# design.net
KiCad netlist of a schematic drawn in Altium Designer
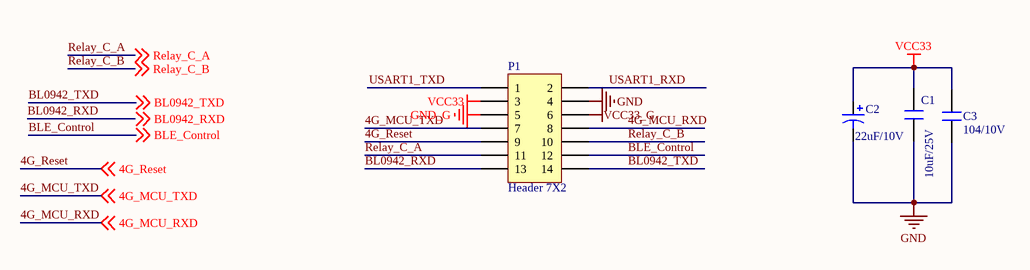
[diagram p0: 连接.SchDoc]

(export (version "E")
  (design (tool "Eeschema 10.0.6"))
  (components
    (comp (ref "C1") (value "10uF/25V") (footprint "0603R") (libsource (lib "ES_Schematic") (part "CAP")))
    (comp (ref "C2")
      (value "22uF/10V")
      (footprint "0805R")
      (description "Polarized Capacitor (Radial)")
      (fields (field (name "PUBLISHER") "Altium Limited"))
      (libsource (lib "Miscellaneous Devices") (part "Cap Pol1"))
    )
    (comp (ref "C3") (value "104/10V") (footprint "0603R") (libsource (lib "ES_Schematic") (part "CAP_1")))
    (comp (ref "P1")
      (value "Header 7X2")
      (footprint "HDR2X7")
      (description "Header, 7-Pin, Dual row")
      (fields (field (name "PUBLISHER") "Altium Limited"))
      (libsource (lib "Miscellaneous Connectors") (part "Header 7X2"))
    )
  )
  (nets
    (net (code "1") (name "/USART1_RXD") (class "Default")
      (node (ref "P1") (pin "2") (pinfunction "2_2") (pintype "passive"))
    )
    (net (code "2") (name "/USART1_TXD") (class "Default")
      (node (ref "P1") (pin "1") (pinfunction "1_1") (pintype "passive"))
    )
    (net (code "3") (name "4G_MCU_RXD") (class "Default")
      (node (ref "P1") (pin "8") (pinfunction "8_8") (pintype "passive"))
    )
    (net (code "4") (name "4G_MCU_TXD") (class "Default")
      (node (ref "P1") (pin "7") (pinfunction "7_7") (pintype "passive"))
    )
    (net (code "5") (name "4G_Reset") (class "Default")
      (node (ref "P1") (pin "9") (pinfunction "9_9") (pintype "passive"))
    )
    (net (code "6") (name "BL0942_RXD") (class "Default")
      (node (ref "P1") (pin "13") (pinfunction "13_13") (pintype "passive"))
    )
    (net (code "7") (name "BL0942_TXD") (class "Default")
      (node (ref "P1") (pin "14") (pinfunction "14_14") (pintype "passive"))
    )
    (net (code "8") (name "BLE_Control") (class "Default")
      (node (ref "P1") (pin "12") (pinfunction "12_12") (pintype "passive"))
    )
    (net (code "9") (name "GND") (class "Default")
      (node (ref "C1") (pin "1") (pinfunction "1_1") (pintype "passive"))
      (node (ref "C2") (pin "2") (pinfunction "2_2") (pintype "passive"))
      (node (ref "C3") (pin "1") (pinfunction "1_1") (pintype "passive"))
      (node (ref "P1") (pin "4") (pinfunction "4_4") (pintype "passive"))
    )
    (net (code "10") (name "GND_G") (class "Default")
      (node (ref "P1") (pin "5") (pinfunction "5_5") (pintype "passive"))
    )
    (net (code "11") (name "Relay_C_A") (class "Default")
      (node (ref "P1") (pin "11") (pinfunction "11_11") (pintype "passive"))
    )
    (net (code "12") (name "Relay_C_B") (class "Default")
      (node (ref "P1") (pin "10") (pinfunction "10_10") (pintype "passive"))
    )
    (net (code "13") (name "VCC33") (class "Default")
      (node (ref "C1") (pin "2") (pinfunction "2_2") (pintype "passive"))
      (node (ref "C2") (pin "1") (pinfunction "1_1") (pintype "passive"))
      (node (ref "C3") (pin "2") (pinfunction "2_2") (pintype "passive"))
      (node (ref "P1") (pin "3") (pinfunction "3_3") (pintype "passive"))
    )
    (net (code "14") (name "VCC33_G") (class "Default")
      (node (ref "P1") (pin "6") (pinfunction "6_6") (pintype "passive"))
    )
  )
)
